# openSX70-FTDI-232RL-Basic-5V.net
KiCad netlist of a schematic drawn in EAGLE
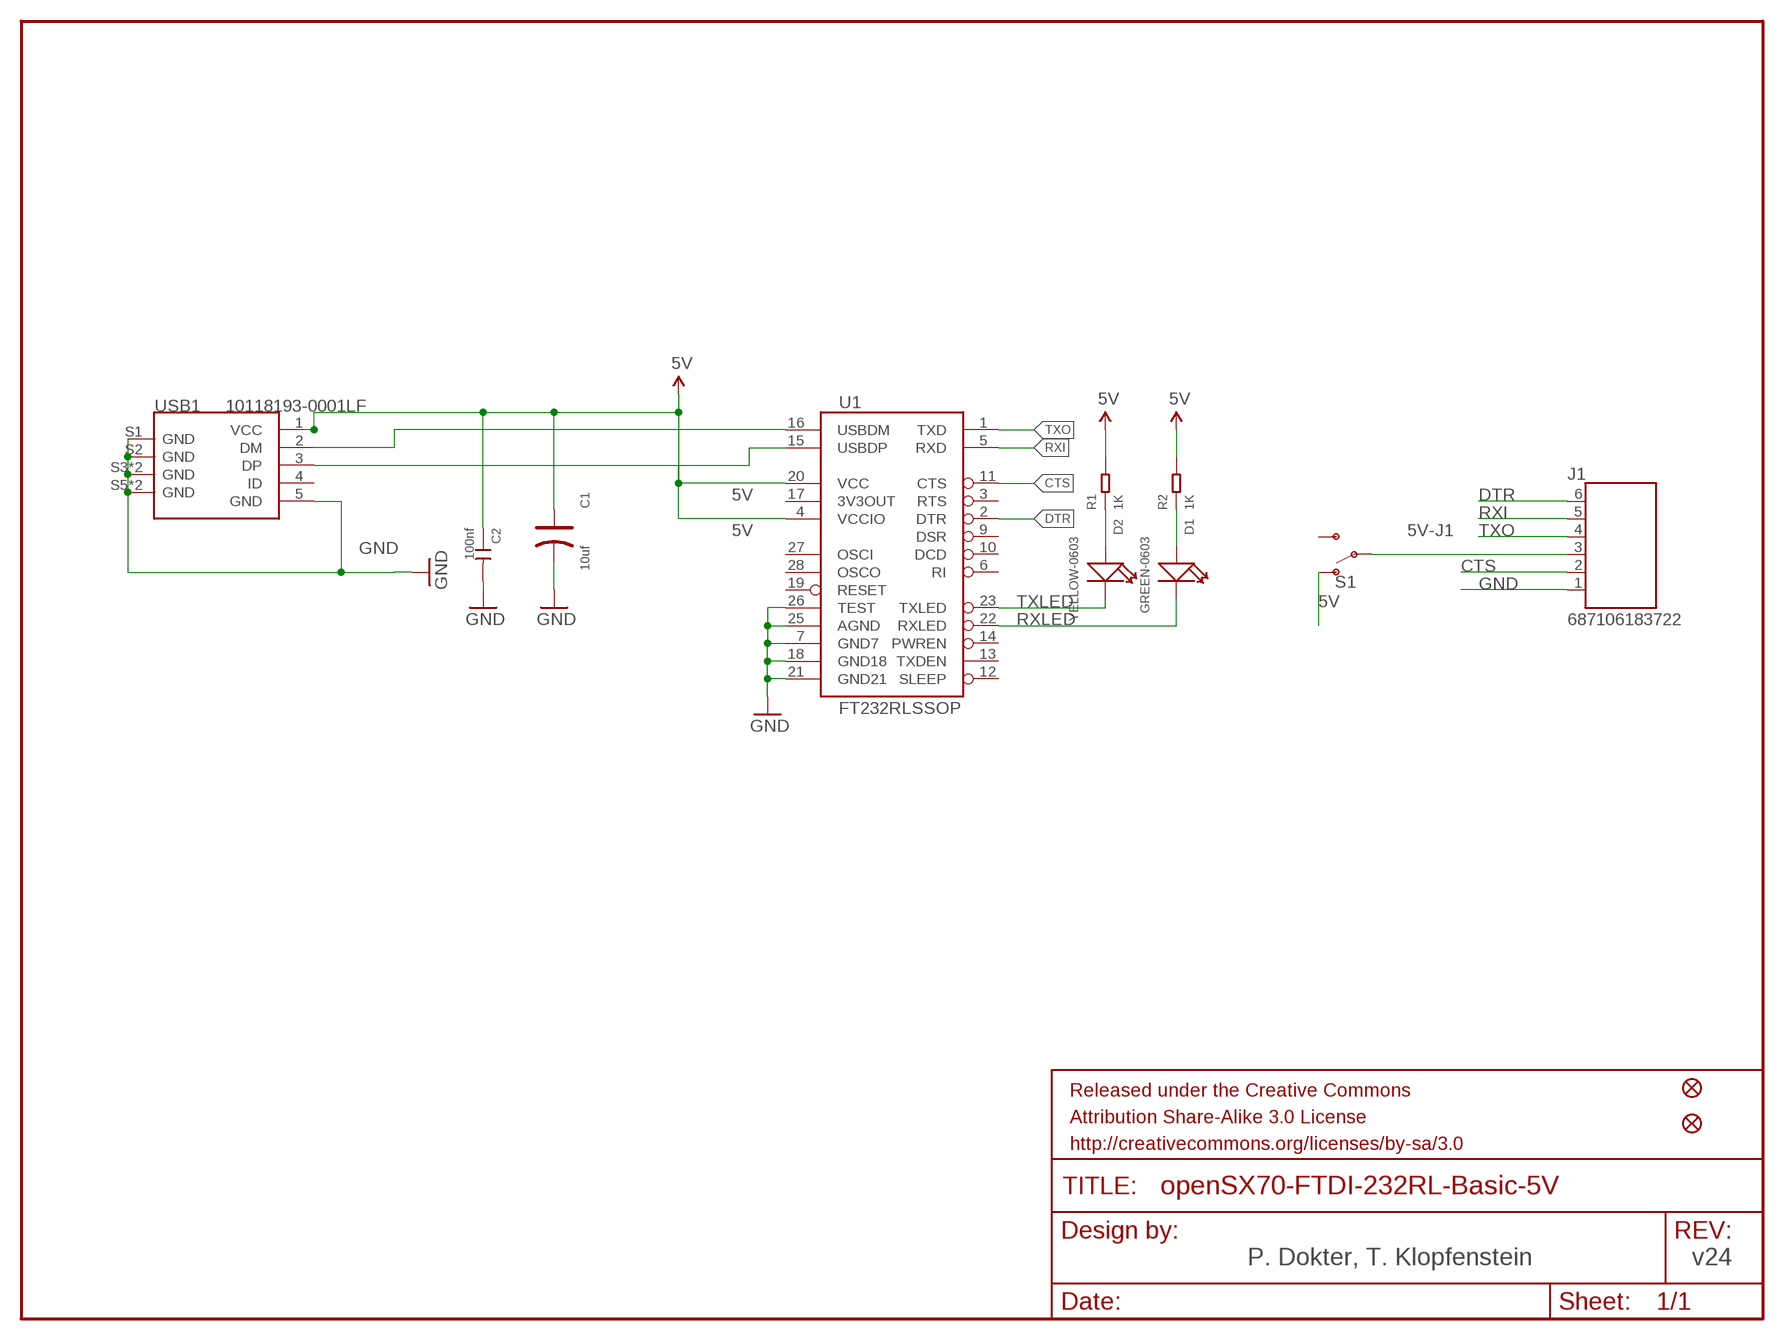
[diagram p0: schematic, sheet 1]

(export (version "E")
  (design (tool "Eeschema 10.0.6"))
  (components
    (comp (ref "C1")
      (value "10uf")
      (footprint "eagle-import:AVX-A")
      (fields (field (name "MPN") "TAJA106K016RNJ"))
      (libsource (lib "eagle-import") (part "TANTALUM-SMD-10UF-16V-10%(AVX-A)"))
    )
    (comp (ref "C2")
      (value "100nf")
      (footprint "eagle-import:C0603")
      (fields (field (name "MPN") "CC0603KRX7R9BB104"))
      (libsource (lib "eagle-import") (part "CERAMIC-100NF-50V-10%-X7R(0603)"))
    )
    (comp (ref "D1")
      (value "GREEN-0603")
      (footprint "eagle-import:LED-0603")
      (fields (field (name "MPN") "19-217-G7C-AN1P2-3T"))
      (libsource (lib "eagle-import") (part "SMD-LED-CLEAR-GREEN(0603)"))
    )
    (comp (ref "D2")
      (value "YELLOW-0603")
      (footprint "eagle-import:LED-0603")
      (fields (field (name "MPN") "19-217-Y5C-AM1N1VY-3T"))
      (libsource (lib "eagle-import") (part "SMD-LED-CLEAR-YELLOW(0603)"))
    )
    (comp (ref "FRAME1")
      (value "FRAME-LETTER")
      (footprint "eagle-import:CREATIVE_COMMONS")
      (libsource (lib "eagle-import") (part "FRAME-LETTER"))
    )
    (comp (ref "J1")
      (value "687106183722")
      (footprint "eagle-import:687106183722")
      (fields (field (name "MF") "Wurth Electronics"))
      (libsource (lib "eagle-import") (part "687106183722"))
    )
    (comp (ref "JP3")
      (value "FIDUCIAL1X2")
      (footprint "eagle-import:FIDUCIAL-1X2")
      (libsource (lib "eagle-import") (part "FIDUCIAL1X2"))
    )
    (comp (ref "JP5")
      (value "FIDUCIAL1X2")
      (footprint "eagle-import:FIDUCIAL-1X2")
      (libsource (lib "eagle-import") (part "FIDUCIAL1X2"))
    )
    (comp (ref "R1")
      (value "1K")
      (footprint "eagle-import:R0603")
      (fields (field (name "MPN") "RC0603FR-071KL"))
      (libsource (lib "eagle-import") (part "SMD-RES-1K-1%-1/10W(0603)"))
    )
    (comp (ref "R2")
      (value "1K")
      (footprint "eagle-import:R0603")
      (fields (field (name "MPN") "RC0603FR-071KL"))
      (libsource (lib "eagle-import") (part "SMD-RES-1K-1%-1/10W(0603)"))
    )
    (comp (ref "S1")
      (value "SWITCH-SPDT-SMD-RIGHT-ANGLE")
      (footprint "eagle-import:SWITCH_SPST_SMD_A")
      (libsource (lib "eagle-import") (part "SWITCH-SPDT-SMD-RIGHT-ANGLE"))
    )
    (comp (ref "U1")
      (value "FT232RLSSOP")
      (footprint "eagle-import:SSOP28DB")
      (libsource (lib "eagle-import") (part "FT232RLSSOP"))
    )
    (comp (ref "USB1")
      (value "10118193-0001LF")
      (footprint "eagle-import:MICRO-USB5+6P-SMD-0.65-B")
      (libsource (lib "eagle-import") (part "MICRO-USB-SMD-B-(10118193-0001LF)"))
    )
  )
  (nets
    (net (code "1") (name "/5V-J1") (class "Default")
      (node (ref "J1") (pin "3") (pinfunction "4_3") (pintype "passive"))
      (node (ref "S1") (pin "2") (pinfunction "P_2") (pintype "passive"))
    )
    (net (code "2") (name "/RXLED") (class "Default")
      (node (ref "D1") (pin "-") (pinfunction "-_-") (pintype "passive"))
      (node (ref "U1") (pin "22") (pinfunction "RXLED_22") (pintype "input"))
    )
    (net (code "3") (name "/TXLED") (class "Default")
      (node (ref "D2") (pin "-") (pinfunction "-_-") (pintype "passive"))
      (node (ref "U1") (pin "23") (pinfunction "TXLED_23") (pintype "input"))
    )
    (net (code "4") (name "5V") (class "Default")
      (node (ref "C1") (pin "+") (pinfunction "+_+") (pintype "passive"))
      (node (ref "C2") (pin "1") (pinfunction "1_1") (pintype "passive"))
      (node (ref "R1") (pin "2") (pinfunction "2_2") (pintype "passive"))
      (node (ref "R2") (pin "2") (pinfunction "2_2") (pintype "passive"))
      (node (ref "S1") (pin "1") (pinfunction "O_1") (pintype "passive"))
      (node (ref "U1") (pin "20") (pinfunction "VCC_20") (pintype "power_in"))
      (node (ref "U1") (pin "4") (pinfunction "VCCIO_4") (pintype "power_in"))
      (node (ref "USB1") (pin "1") (pinfunction "VCC_1") (pintype "bidirectional"))
    )
    (net (code "5") (name "CTS") (class "Default")
      (node (ref "J1") (pin "2") (pinfunction "5_2") (pintype "passive"))
      (node (ref "U1") (pin "11") (pinfunction "CTS_11") (pintype "input"))
    )
    (net (code "6") (name "DTR") (class "Default")
      (node (ref "J1") (pin "6") (pinfunction "1_6") (pintype "passive"))
      (node (ref "U1") (pin "2") (pinfunction "DTR_2") (pintype "output"))
    )
    (net (code "7") (name "GND") (class "Default")
      (node (ref "C1") (pin "-") (pinfunction "-_-") (pintype "passive"))
      (node (ref "C2") (pin "2") (pinfunction "2_2") (pintype "passive"))
      (node (ref "J1") (pin "1") (pinfunction "6_1") (pintype "passive"))
      (node (ref "U1") (pin "18") (pinfunction "GND18_18") (pintype "power_in"))
      (node (ref "U1") (pin "21") (pinfunction "GND21_21") (pintype "power_in"))
      (node (ref "U1") (pin "25") (pinfunction "AGND_25") (pintype "power_in"))
      (node (ref "U1") (pin "26") (pinfunction "TEST_26") (pintype "input"))
      (node (ref "U1") (pin "7") (pinfunction "GND7_7") (pintype "power_in"))
      (node (ref "USB1") (pin "5") (pinfunction "GND_5") (pintype "bidirectional"))
      (node (ref "USB1") (pin "S1") (pinfunction "GND_S1") (pintype "bidirectional"))
      (node (ref "USB1") (pin "S2") (pinfunction "GND_S2") (pintype "bidirectional"))
      (node (ref "USB1") (pin "S3") (pinfunction "GND_S3") (pintype "bidirectional"))
      (node (ref "USB1") (pin "S4") (pinfunction "GND_S4") (pintype "bidirectional"))
      (node (ref "USB1") (pin "S5") (pinfunction "GND_S5") (pintype "bidirectional"))
      (node (ref "USB1") (pin "S6") (pinfunction "GND_S6") (pintype "bidirectional"))
    )
    (net (code "8") (name "Net-(D1-Pad+)") (class "Default")
      (node (ref "D1") (pin "+") (pinfunction "+_+") (pintype "passive"))
      (node (ref "R2") (pin "1") (pinfunction "1_1") (pintype "passive"))
    )
    (net (code "9") (name "Net-(D2-Pad+)") (class "Default")
      (node (ref "D2") (pin "+") (pinfunction "+_+") (pintype "passive"))
      (node (ref "R1") (pin "1") (pinfunction "1_1") (pintype "passive"))
    )
    (net (code "10") (name "Net-(U1-USBDM)") (class "Default")
      (node (ref "U1") (pin "16") (pinfunction "USBDM_16") (pintype "bidirectional"))
      (node (ref "USB1") (pin "2") (pinfunction "DM_2") (pintype "bidirectional"))
    )
    (net (code "11") (name "Net-(U1-USBDP)") (class "Default")
      (node (ref "U1") (pin "15") (pinfunction "USBDP_15") (pintype "bidirectional"))
      (node (ref "USB1") (pin "3") (pinfunction "DP_3") (pintype "bidirectional"))
    )
    (net (code "12") (name "RXI") (class "Default")
      (node (ref "J1") (pin "5") (pinfunction "2_5") (pintype "passive"))
      (node (ref "U1") (pin "5") (pinfunction "RXD_5") (pintype "input"))
    )
    (net (code "13") (name "TXO") (class "Default")
      (node (ref "J1") (pin "4") (pinfunction "3_4") (pintype "passive"))
      (node (ref "U1") (pin "1") (pinfunction "TXD_1") (pintype "output"))
    )
    (net (code "14") (name "unconnected-(S1-S-Pad3)") (class "Default")
      (node (ref "S1") (pin "3") (pinfunction "S_3") (pintype "passive"))
    )
    (net (code "15") (name "unconnected-(U1-3V3OUT-Pad17)") (class "Default")
      (node (ref "U1") (pin "17") (pinfunction "3V3OUT_17") (pintype "output"))
    )
    (net (code "16") (name "unconnected-(U1-DCD-Pad10)") (class "Default")
      (node (ref "U1") (pin "10") (pinfunction "DCD_10") (pintype "input"))
    )
    (net (code "17") (name "unconnected-(U1-DSR-Pad9)") (class "Default")
      (node (ref "U1") (pin "9") (pinfunction "DSR_9") (pintype "input"))
    )
    (net (code "18") (name "unconnected-(U1-OSCI-Pad27)") (class "Default")
      (node (ref "U1") (pin "27") (pinfunction "OSCI_27") (pintype "input"))
    )
    (net (code "19") (name "unconnected-(U1-OSCO-Pad28)") (class "Default")
      (node (ref "U1") (pin "28") (pinfunction "OSCO_28") (pintype "output"))
    )
    (net (code "20") (name "unconnected-(U1-PWREN-Pad14)") (class "Default")
      (node (ref "U1") (pin "14") (pinfunction "PWREN_14") (pintype "input"))
    )
    (net (code "21") (name "unconnected-(U1-RESET-Pad19)") (class "Default")
      (node (ref "U1") (pin "19") (pinfunction "RESET_19") (pintype "input"))
    )
    (net (code "22") (name "unconnected-(U1-RI-Pad6)") (class "Default")
      (node (ref "U1") (pin "6") (pinfunction "RI_6") (pintype "input"))
    )
    (net (code "23") (name "unconnected-(U1-RTS-Pad3)") (class "Default")
      (node (ref "U1") (pin "3") (pinfunction "RTS_3") (pintype "output"))
    )
    (net (code "24") (name "unconnected-(U1-SLEEP-Pad12)") (class "Default")
      (node (ref "U1") (pin "12") (pinfunction "SLEEP_12") (pintype "input"))
    )
    (net (code "25") (name "unconnected-(U1-TXDEN-Pad13)") (class "Default")
      (node (ref "U1") (pin "13") (pinfunction "TXDEN_13") (pintype "input"))
    )
    (net (code "26") (name "unconnected-(USB1-ID-Pad4)") (class "Default")
      (node (ref "USB1") (pin "4") (pinfunction "ID_4") (pintype "bidirectional"))
    )
  )
)
